# SMA_TL.net
KiCad netlist of a schematic drawn in Altium Designer
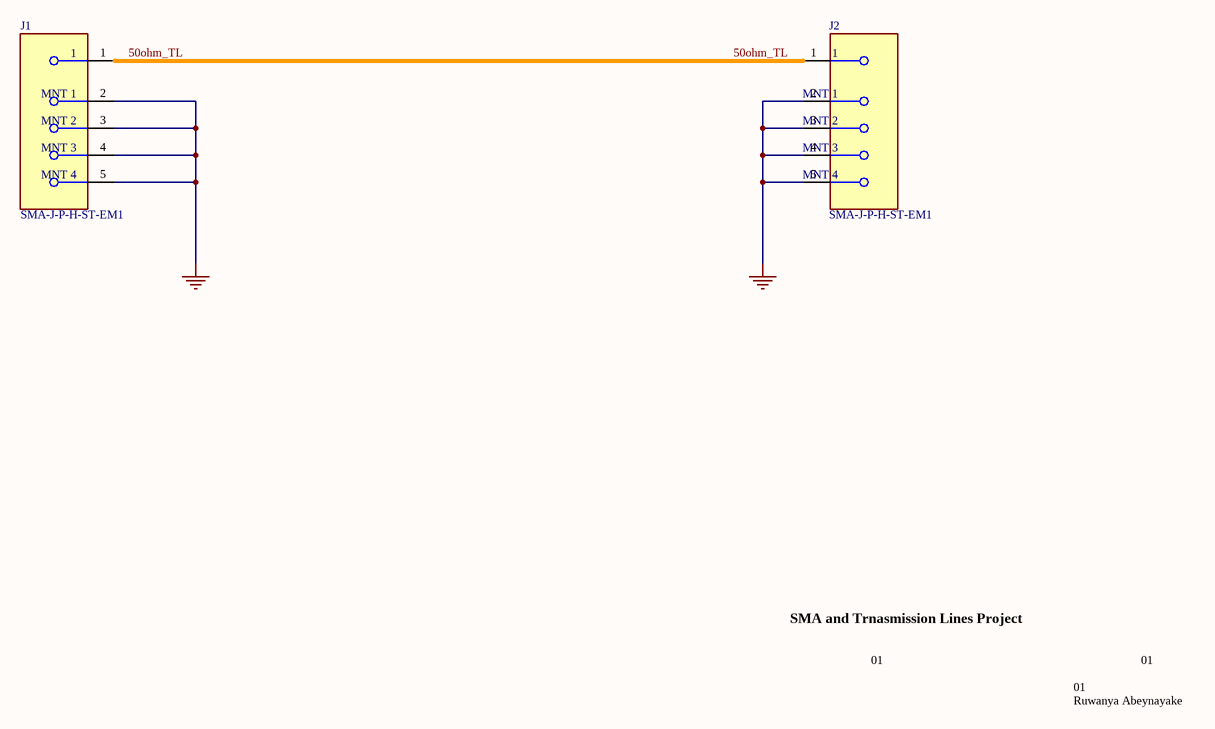
[diagram p0: SMA_TL.SchDoc]

(export (version "E")
  (design (tool "Eeschema 10.0.6"))
  (components
    (comp (ref "J1")
      (value "SMA-J-P-H-ST-EM1")
      (footprint "FP-SMA-J-P-H-ST-EM1-MFG")
      (description "CONN SMA JACK STR 50OHM EDGE MNT")
      (libsource (lib "") (part "c65b8a639cdaef1819ea20b5466f8fa_1"))
    )
    (comp (ref "J2")
      (value "SMA-J-P-H-ST-EM1")
      (footprint "FP-SMA-J-P-H-ST-EM1-MFG")
      (description "CONN SMA JACK STR 50OHM EDGE MNT")
      (libsource (lib "Altium Content Vault") (part "c65b8a639cdaef1819ea20b5466f8fa"))
    )
  )
  (nets
    (net (code "1") (name "/50ohm_TL") (class "Default")
      (node (ref "J1") (pin "1") (pinfunction "1_1") (pintype "passive"))
      (node (ref "J2") (pin "1") (pinfunction "1_1") (pintype "passive"))
    )
    (net (code "2") (name "GND") (class "Default")
      (node (ref "J1") (pin "2") (pinfunction "MNT_1_2") (pintype "passive"))
      (node (ref "J1") (pin "3") (pinfunction "MNT_2_3") (pintype "passive"))
      (node (ref "J1") (pin "4") (pinfunction "MNT_3_4") (pintype "passive"))
      (node (ref "J1") (pin "5") (pinfunction "MNT_4_5") (pintype "passive"))
      (node (ref "J2") (pin "2") (pinfunction "MNT_1_2") (pintype "passive"))
      (node (ref "J2") (pin "3") (pinfunction "MNT_2_3") (pintype "passive"))
      (node (ref "J2") (pin "4") (pinfunction "MNT_3_4") (pintype "passive"))
      (node (ref "J2") (pin "5") (pinfunction "MNT_4_5") (pintype "passive"))
    )
  )
)
